# Power.net
KiCad netlist of a schematic drawn in Altium Designer
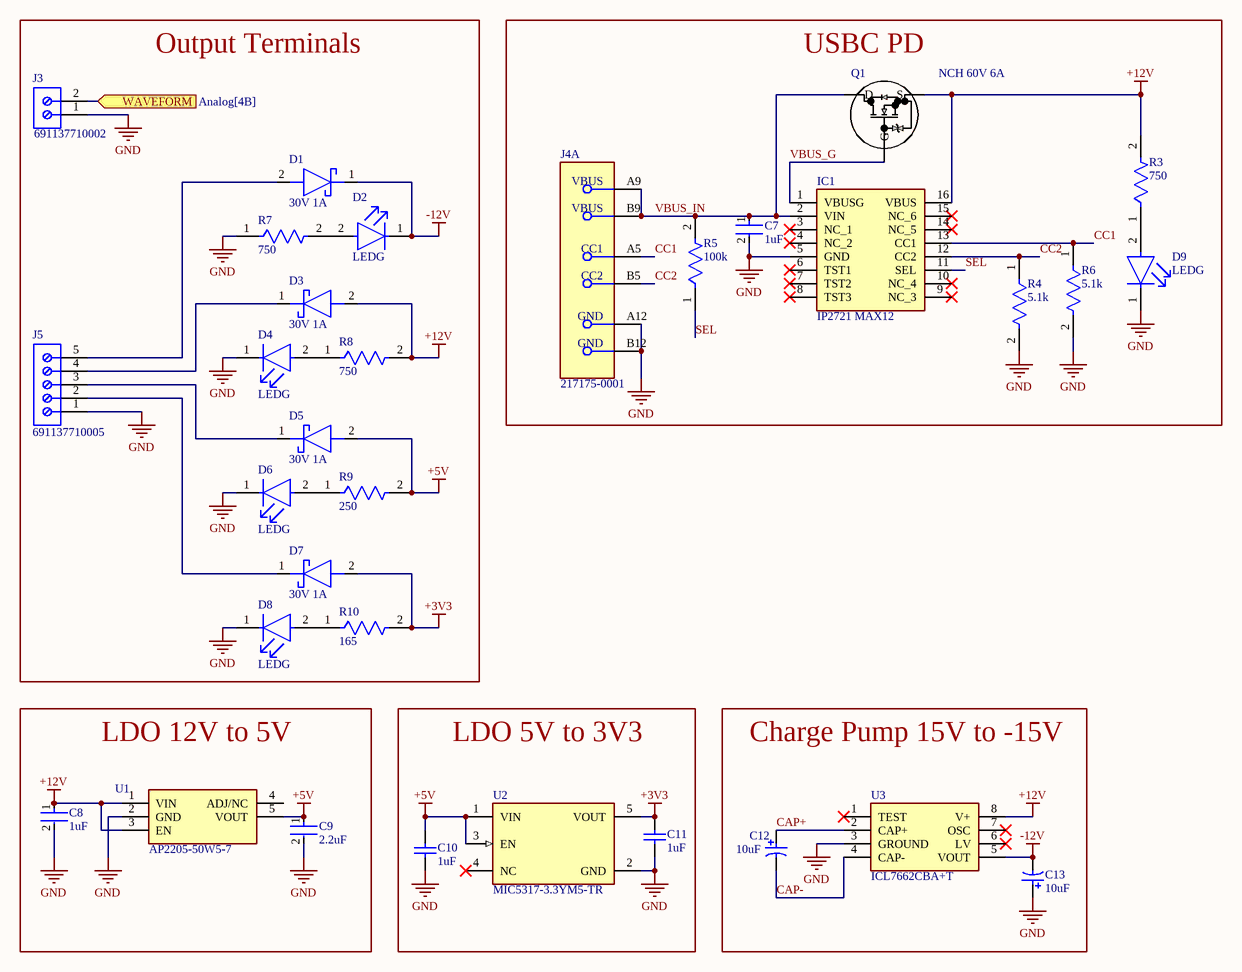
[diagram p0: Power.SchDoc]

(export (version "E")
  (design (tool "Eeschema 10.0.6"))
  (components
    (comp (ref "C7")
      (value "1uF")
      (footprint "FP-CGA5L-0_3-0_1-IPC_B")
      (description "Cap Ceramic 1uF 25V X7R 20% Pad SMD 1206 +125°C Automotive T/R")
      (fields (field (name "TOLERANCE") "20%"))
      (libsource (lib "Altium Content Vault") (part "b4654b650e69147ec39a6b967a45e02"))
    )
    (comp (ref "C8")
      (value "1uF")
      (footprint "FP-CGA5L-0_3-0_1-IPC_B")
      (description "Cap Ceramic 1uF 25V X7R 20% Pad SMD 1206 +125°C Automotive T/R")
      (fields (field (name "TOLERANCE") "20%"))
      (libsource (lib "Altium Content Vault") (part "b4654b650e69147ec39a6b967a45e02"))
    )
    (comp (ref "C9")
      (value "2.2uF")
      (footprint "FP-C0402-BB-MFG")
      (description "C0402")
      (fields
        (field (name "OCTOPART") "https://octopart.com/c0402c132k8gactu-kemet-56745629")
        (field (name "TOLERANCE") "0.1")
      )
      (libsource (lib "Altium Content Vault") (part "b4654b650e69147ec39a6b967a45e02"))
    )
    (comp (ref "C10")
      (value "1uF")
      (footprint "CAPC1206(3216)130_N")
      (description "CAP 1uF 10V ±5% 1206 (3216 Metric) Thickness 1.3mm SMD")
      (fields (field (name "TOLERANCE") "Â±5%"))
      (libsource (lib "Altium Content Vault") (part "CAP"))
    )
    (comp (ref "C11")
      (value "1uF")
      (footprint "CAPC1206(3216)130_N")
      (description "CAP 1uF 10V ±5% 1206 (3216 Metric) Thickness 1.3mm SMD")
      (fields (field (name "TOLERANCE") "Â±5%"))
      (libsource (lib "Altium Content Vault") (part "CAP"))
    )
    (comp (ref "C12")
      (value "10uF")
      (footprint "VISH-293D-E_L")
      (fields (field (name "MANUFACTURER") "Vishay") (field (name "VOLTAGE") "50VDC"))
      (libsource (lib "Altium Content Vault") (part "CAP-P-2"))
    )
    (comp (ref "C13")
      (value "10uF")
      (footprint "VISH-293D-E_L")
      (fields (field (name "MANUFACTURER") "Vishay") (field (name "VOLTAGE") "50VDC"))
      (libsource (lib "Altium Content Vault") (part "CAP-P-2"))
    )
    (comp (ref "D1")
      (value "30V 1A")
      (footprint "SamacSys:1SS357TPH3F")
      (description "Schottky Diode")
      (fields
        (field (name "MANUFACTURER_PART_NUMBER") "CUS10S30,H3F")
        (field (name "MOUSER PART NUMBER") "757-CUS10S30H3F")
      )
      (libsource (lib "*") (part "CUS10S30,H3F"))
    )
    (comp (ref "D2")
      (value "LEDG")
      (footprint "FP-LTST-C170GKT-MFG")
      (description "LED GREEN CLEAR SMD")
      (fields (field (name "VOLTAGE") "5V"))
      (libsource (lib "Altium Content Vault") (part "8706943c75ba83719d021d2fdc84c58"))
    )
    (comp (ref "D3")
      (value "30V 1A")
      (footprint "SamacSys:1SS357TPH3F")
      (description "Schottky Diode")
      (fields
        (field (name "MANUFACTURER_PART_NUMBER") "CUS10S30,H3F")
        (field (name "MOUSER PART NUMBER") "757-CUS10S30H3F")
      )
      (libsource (lib "*") (part "CUS10S30,H3F"))
    )
    (comp (ref "D4")
      (value "LEDG")
      (footprint "FP-LTST-C170GKT-MFG")
      (description "LED GREEN CLEAR SMD")
      (fields (field (name "VOLTAGE") "5V"))
      (libsource (lib "Altium Content Vault") (part "8706943c75ba83719d021d2fdc84c58"))
    )
    (comp (ref "D5")
      (value "30V 1A")
      (footprint "SamacSys:1SS357TPH3F")
      (description "Schottky Diode")
      (fields
        (field (name "MANUFACTURER_PART_NUMBER") "CUS10S30,H3F")
        (field (name "MOUSER PART NUMBER") "757-CUS10S30H3F")
      )
      (libsource (lib "*") (part "CUS10S30,H3F"))
    )
    (comp (ref "D6")
      (value "LEDG")
      (footprint "FP-LTST-C170GKT-MFG")
      (description "LED GREEN CLEAR SMD")
      (fields (field (name "VOLTAGE") "5V"))
      (libsource (lib "Altium Content Vault") (part "8706943c75ba83719d021d2fdc84c58"))
    )
    (comp (ref "D7")
      (value "30V 1A")
      (footprint "SamacSys:1SS357TPH3F")
      (description "Schottky Diode")
      (fields
        (field (name "MANUFACTURER_PART_NUMBER") "CUS10S30,H3F")
        (field (name "MOUSER PART NUMBER") "757-CUS10S30H3F")
      )
      (libsource (lib "*") (part "CUS10S30,H3F"))
    )
    (comp (ref "D8")
      (value "LEDG")
      (footprint "FP-LTST-C170GKT-MFG")
      (description "LED GREEN CLEAR SMD")
      (fields (field (name "VOLTAGE") "5V"))
      (libsource (lib "Altium Content Vault") (part "8706943c75ba83719d021d2fdc84c58"))
    )
    (comp (ref "D9")
      (value "LEDG")
      (footprint "FP-LTST-C170GKT-MFG")
      (description "LED GREEN CLEAR SMD")
      (fields (field (name "VOLTAGE") "5V"))
      (libsource (lib "Altium Content Vault") (part "8706943c75ba83719d021d2fdc84c58"))
    )
    (comp (ref "IC1")
      (value "IP2721 MAX12")
      (footprint "SamacSys:SOP65P640X120-16N")
      (description "Integrated Circuit")
      (fields (field (name "MANUFACTURER_PART_NUMBER") "IP2721"))
      (libsource (lib "*") (part "IP2721"))
    )
    (comp (ref "J3")
      (value "691137710002")
      (footprint "691137710002")
      (libsource (lib "Altium Content Vault") (part "TBL - 1R - 02P - Screw"))
    )
    (comp (ref "J4")
      (value "217175-0001")
      (footprint "FP-217175-0001-MFG")
      (description "CONN RCP USB2.0 C 6+18P SMD RA")
      (libsource (lib "Altium Content Vault") (part "6a66c69350f09309f94811689c98437"))
    )
    (comp (ref "J5")
      (value "691137710005")
      (footprint "691137710005")
      (libsource (lib "Altium Content Vault") (part "TBL - 1R - 05P - Screw"))
    )
    (comp (ref "Q1")
      (value "NCH 60V 6A")
      (footprint "SOT-323F_2-2U1S_UFM_TOS")
      (description "N-ch MOSFET, 60 V, 6.0 A, 0.036 Î©@10V, SOT-323F(UFM)")
      (fields
        (field (name "MANUFACTURER_PART_NUMBER") "SSM3K341TU,LF")
        (field (name "COPYRIGHT") "Copyright (C) 2025 Ultra Librarian. All rights reserved.")
      )
      (libsource (lib "Connectors") (part "SSM3K341TU,LF"))
    )
    (comp (ref "R3")
      (value "750")
      (footprint "FP-AT0805-IPC_C")
      (description "Thin Film Chip Resistors Automotive Grade 10kΩ 0.1% 50ppm/°C 0805")
      (libsource (lib "Altium Content Vault") (part "1029c3af85768c4190bb7ad29bc67b5"))
    )
    (comp (ref "R4")
      (value "5.1k")
      (footprint "FP-TFCR0603-IPC_A")
      (description "RES Thin Film,  5.1kΩ, 0.25%, 0.1W, 25ppm/°C, 0603")
      (libsource (lib "Altium Content Vault") (part "1029c3af85768c4190bb7ad29bc67b5"))
    )
    (comp (ref "R5")
      (value "100k")
      (footprint "FP-MCU0805-IPC_B")
      (description "0805")
      (libsource (lib "Altium Content Vault") (part "1029c3af85768c4190bb7ad29bc67b5"))
    )
    (comp (ref "R6")
      (value "5.1k")
      (footprint "FP-TFCR0603-IPC_A")
      (description "RES Thin Film,  5.1kΩ, 0.25%, 0.1W, 25ppm/°C, 0603")
      (libsource (lib "Altium Content Vault") (part "1029c3af85768c4190bb7ad29bc67b5"))
    )
    (comp (ref "R7")
      (value "750")
      (footprint "FP-RMCF0805-MFG")
      (description "6.8kΩ ±5% 0.125W 0805 Thick Film Chip Resistor AEC-Q200 compliant")
      (fields (field (name "TOLERANCE") "5%"))
      (libsource (lib "Altium Content Vault") (part "1029c3af85768c4190bb7ad29bc67b5"))
    )
    (comp (ref "R8")
      (value "750")
      (footprint "FP-RMCF0805-MFG")
      (description "6.8kΩ ±5% 0.125W 0805 Thick Film Chip Resistor AEC-Q200 compliant")
      (fields (field (name "TOLERANCE") "5%"))
      (libsource (lib "Altium Content Vault") (part "1029c3af85768c4190bb7ad29bc67b5"))
    )
    (comp (ref "R9")
      (value "250")
      (footprint "FP-RMCF0805-MFG")
      (description "0805 250 Ohms 0.25W")
      (fields (field (name "TOLERANCE") "5%"))
      (libsource (lib "Altium Content Vault") (part "1029c3af85768c4190bb7ad29bc67b5"))
    )
    (comp (ref "R10")
      (value "165")
      (footprint "FP-TFCR0603-IPC_B")
      (description "RES Thin Film,  620Ω, 0.25%, 0.1W, 25ppm/°C, 0603")
      (libsource (lib "Altium Content Vault") (part "1029c3af85768c4190bb7ad29bc67b5"))
    )
    (comp (ref "U1")
      (value "AP2205-50W5-7")
      (footprint "SamacSys:SOT95P285X140-5N")
      (description "Integrated Circuit")
      (fields (field (name "MOUSER PART NUMBER") "621-AP2205-50W5-7"))
      (libsource (lib "*") (part "AP2205-50W5-7"))
    )
    (comp (ref "U2")
      (value "MIC5317-3.3YM5-TR")
      (footprint "FP-SOT23-5LD-PL-1-MFG")
      (description "IC REG LINEAR 3.3V 150MA SOT23-5")
      (libsource (lib "Altium Content Vault") (part "0a093dae7315cdc977fd108dde87457"))
    )
    (comp (ref "U3")
      (value "ICL7662CBA+T")
      (footprint "SamacSys:SOIC127P600X175-8N")
      (description "Integrated Circuit")
      (fields (field (name "MOUSER PART NUMBER") "700-ICL7662CBAT"))
      (libsource (lib "*") (part "ICL7662CBA+T"))
    )
  )
  (nets
    (net (code "1") (name "+3V3") (class "Default")
      (node (ref "C11") (pin "2") (pinfunction "2_2") (pintype "passive"))
      (node (ref "D7") (pin "2") (pinfunction "A_2") (pintype "passive"))
      (node (ref "R10") (pin "2") (pinfunction "2_2") (pintype "passive"))
      (node (ref "U2") (pin "5") (pinfunction "VOUT_5") (pintype "power_in"))
    )
    (net (code "2") (name "+5V") (class "Default")
      (node (ref "C10") (pin "2") (pinfunction "2_2") (pintype "passive"))
      (node (ref "C9") (pin "1") (pinfunction "1_1") (pintype "passive"))
      (node (ref "D5") (pin "2") (pinfunction "A_2") (pintype "passive"))
      (node (ref "R9") (pin "2") (pinfunction "2_2") (pintype "passive"))
      (node (ref "U1") (pin "5") (pinfunction "VOUT_5") (pintype "passive"))
      (node (ref "U2") (pin "1") (pinfunction "VIN_1") (pintype "power_in"))
      (node (ref "U2") (pin "3") (pinfunction "EN_3") (pintype "input"))
    )
    (net (code "3") (name "+12V") (class "Default")
      (node (ref "C8") (pin "1") (pinfunction "1_1") (pintype "passive"))
      (node (ref "D3") (pin "2") (pinfunction "A_2") (pintype "passive"))
      (node (ref "IC1") (pin "16") (pinfunction "VBUS_16") (pintype "passive"))
      (node (ref "Q1") (pin "2") (pinfunction "S_2") (pintype "passive"))
      (node (ref "R3") (pin "2") (pinfunction "2_2") (pintype "passive"))
      (node (ref "R8") (pin "2") (pinfunction "2_2") (pintype "passive"))
      (node (ref "U1") (pin "1") (pinfunction "VIN_1") (pintype "passive"))
      (node (ref "U1") (pin "3") (pinfunction "EN_3") (pintype "passive"))
      (node (ref "U3") (pin "8") (pinfunction "V+_8") (pintype "passive"))
    )
    (net (code "4") (name "-12V") (class "Default")
      (node (ref "C13") (pin "2") (pinfunction "2_2") (pintype "passive"))
      (node (ref "D1") (pin "1") (pinfunction "K_1") (pintype "passive"))
      (node (ref "D2") (pin "1") (pinfunction "C_1") (pintype "passive"))
      (node (ref "U3") (pin "5") (pinfunction "VOUT_5") (pintype "passive"))
    )
    (net (code "5") (name "/CAP+") (class "Default")
      (node (ref "C12") (pin "1") (pinfunction "1_1") (pintype "passive"))
      (node (ref "U3") (pin "2") (pinfunction "CAP+_2") (pintype "passive"))
    )
    (net (code "6") (name "/CAP-") (class "Default")
      (node (ref "C12") (pin "2") (pinfunction "2_2") (pintype "passive"))
      (node (ref "U3") (pin "4") (pinfunction "CAP-_4") (pintype "passive"))
    )
    (net (code "7") (name "/CC1") (class "Default")
      (node (ref "IC1") (pin "13") (pinfunction "CC1_13") (pintype "passive"))
      (node (ref "J4") (pin "A5") (pinfunction "CC1_A5") (pintype "passive"))
      (node (ref "R6") (pin "1") (pinfunction "1_1") (pintype "passive"))
    )
    (net (code "8") (name "/CC2") (class "Default")
      (node (ref "IC1") (pin "12") (pinfunction "CC2_12") (pintype "passive"))
      (node (ref "J4") (pin "B5") (pinfunction "CC2_B5") (pintype "passive"))
      (node (ref "R4") (pin "1") (pinfunction "1_1") (pintype "passive"))
    )
    (net (code "9") (name "/SEL") (class "Default")
      (node (ref "IC1") (pin "11") (pinfunction "SEL_11") (pintype "passive"))
      (node (ref "R5") (pin "1") (pinfunction "1_1") (pintype "passive"))
    )
    (net (code "10") (name "/VBUS_G") (class "Default")
      (node (ref "IC1") (pin "1") (pinfunction "VBUSG_1") (pintype "passive"))
      (node (ref "Q1") (pin "1") (pinfunction "G_1") (pintype "passive"))
    )
    (net (code "11") (name "/VBUS_IN") (class "Default")
      (node (ref "C7") (pin "1") (pinfunction "1_1") (pintype "passive"))
      (node (ref "IC1") (pin "2") (pinfunction "VIN_2") (pintype "passive"))
      (node (ref "J4") (pin "A9") (pinfunction "VBUS_A9") (pintype "power_in"))
      (node (ref "J4") (pin "B9") (pinfunction "VBUS_B9") (pintype "power_in"))
      (node (ref "Q1") (pin "3") (pinfunction "D_3") (pintype "passive"))
      (node (ref "R5") (pin "2") (pinfunction "2_2") (pintype "passive"))
    )
    (net (code "12") (name "/WAVEFORM") (class "Default")
      (node (ref "J3") (pin "2") (pinfunction "2_2") (pintype "passive"))
    )
    (net (code "13") (name "GND") (class "Default")
      (node (ref "C10") (pin "1") (pinfunction "1_1") (pintype "passive"))
      (node (ref "C11") (pin "1") (pinfunction "1_1") (pintype "passive"))
      (node (ref "C13") (pin "1") (pinfunction "1_1") (pintype "passive"))
      (node (ref "C7") (pin "2") (pinfunction "2_2") (pintype "passive"))
      (node (ref "C8") (pin "2") (pinfunction "2_2") (pintype "passive"))
      (node (ref "C9") (pin "2") (pinfunction "2_2") (pintype "passive"))
      (node (ref "D4") (pin "1") (pinfunction "C_1") (pintype "passive"))
      (node (ref "D6") (pin "1") (pinfunction "C_1") (pintype "passive"))
      (node (ref "D8") (pin "1") (pinfunction "C_1") (pintype "passive"))
      (node (ref "D9") (pin "1") (pinfunction "C_1") (pintype "passive"))
      (node (ref "IC1") (pin "5") (pinfunction "GND_5") (pintype "passive"))
      (node (ref "J3") (pin "1") (pinfunction "1_1") (pintype "passive"))
      (node (ref "J4") (pin "A12") (pinfunction "GND_A12") (pintype "power_in"))
      (node (ref "J4") (pin "B12") (pinfunction "GND_B12") (pintype "power_in"))
      (node (ref "J5") (pin "1") (pinfunction "1_1") (pintype "passive"))
      (node (ref "R4") (pin "2") (pinfunction "2_2") (pintype "passive"))
      (node (ref "R6") (pin "2") (pinfunction "2_2") (pintype "passive"))
      (node (ref "R7") (pin "1") (pinfunction "1_1") (pintype "passive"))
      (node (ref "U1") (pin "2") (pinfunction "GND_2") (pintype "passive"))
      (node (ref "U2") (pin "2") (pinfunction "GND_2") (pintype "power_in"))
      (node (ref "U3") (pin "3") (pinfunction "GROUND_3") (pintype "passive"))
    )
    (net (code "14") (name "Net-(D1-A)") (class "Default")
      (node (ref "D1") (pin "2") (pinfunction "A_2") (pintype "passive"))
      (node (ref "J5") (pin "5") (pinfunction "5_5") (pintype "passive"))
    )
    (net (code "15") (name "Net-(D2-A)") (class "Default")
      (node (ref "D2") (pin "2") (pinfunction "A_2") (pintype "passive"))
      (node (ref "R7") (pin "2") (pinfunction "2_2") (pintype "passive"))
    )
    (net (code "16") (name "Net-(D3-K)") (class "Default")
      (node (ref "D3") (pin "1") (pinfunction "K_1") (pintype "passive"))
      (node (ref "J5") (pin "4") (pinfunction "4_4") (pintype "passive"))
    )
    (net (code "17") (name "Net-(D4-A)") (class "Default")
      (node (ref "D4") (pin "2") (pinfunction "A_2") (pintype "passive"))
      (node (ref "R8") (pin "1") (pinfunction "1_1") (pintype "passive"))
    )
    (net (code "18") (name "Net-(D5-K)") (class "Default")
      (node (ref "D5") (pin "1") (pinfunction "K_1") (pintype "passive"))
      (node (ref "J5") (pin "3") (pinfunction "3_3") (pintype "passive"))
    )
    (net (code "19") (name "Net-(D6-A)") (class "Default")
      (node (ref "D6") (pin "2") (pinfunction "A_2") (pintype "passive"))
      (node (ref "R9") (pin "1") (pinfunction "1_1") (pintype "passive"))
    )
    (net (code "20") (name "Net-(D7-K)") (class "Default")
      (node (ref "D7") (pin "1") (pinfunction "K_1") (pintype "passive"))
      (node (ref "J5") (pin "2") (pinfunction "2_2") (pintype "passive"))
    )
    (net (code "21") (name "Net-(D8-A)") (class "Default")
      (node (ref "D8") (pin "2") (pinfunction "A_2") (pintype "passive"))
      (node (ref "R10") (pin "1") (pinfunction "1_1") (pintype "passive"))
    )
    (net (code "22") (name "Net-(D9-A)") (class "Default")
      (node (ref "D9") (pin "2") (pinfunction "A_2") (pintype "passive"))
      (node (ref "R3") (pin "1") (pinfunction "1_1") (pintype "passive"))
    )
    (net (code "23") (name "unconnected-(IC1-NC_1-Pad3)") (class "Default")
      (node (ref "IC1") (pin "3") (pinfunction "NC_1_3") (pintype "passive+no_connect"))
    )
    (net (code "24") (name "unconnected-(IC1-NC_2-Pad4)") (class "Default")
      (node (ref "IC1") (pin "4") (pinfunction "NC_2_4") (pintype "passive+no_connect"))
    )
    (net (code "25") (name "unconnected-(IC1-NC_3-Pad9)") (class "Default")
      (node (ref "IC1") (pin "9") (pinfunction "NC_3_9") (pintype "passive+no_connect"))
    )
    (net (code "26") (name "unconnected-(IC1-NC_4-Pad10)") (class "Default")
      (node (ref "IC1") (pin "10") (pinfunction "NC_4_10") (pintype "passive+no_connect"))
    )
    (net (code "27") (name "unconnected-(IC1-NC_5-Pad14)") (class "Default")
      (node (ref "IC1") (pin "14") (pinfunction "NC_5_14") (pintype "passive+no_connect"))
    )
    (net (code "28") (name "unconnected-(IC1-NC_6-Pad15)") (class "Default")
      (node (ref "IC1") (pin "15") (pinfunction "NC_6_15") (pintype "passive+no_connect"))
    )
    (net (code "29") (name "unconnected-(IC1-TST1-Pad6)") (class "Default")
      (node (ref "IC1") (pin "6") (pinfunction "TST1_6") (pintype "passive+no_connect"))
    )
    (net (code "30") (name "unconnected-(IC1-TST2-Pad7)") (class "Default")
      (node (ref "IC1") (pin "7") (pinfunction "TST2_7") (pintype "passive+no_connect"))
    )
    (net (code "31") (name "unconnected-(IC1-TST3-Pad8)") (class "Default")
      (node (ref "IC1") (pin "8") (pinfunction "TST3_8") (pintype "passive+no_connect"))
    )
    (net (code "32") (name "unconnected-(U1-ADJ{slash}NC-Pad4)") (class "Default")
      (node (ref "U1") (pin "4") (pinfunction "ADJ/NC_4") (pintype "passive"))
    )
    (net (code "33") (name "unconnected-(U2-NC-Pad4)") (class "Default")
      (node (ref "U2") (pin "4") (pinfunction "NC_4") (pintype "passive+no_connect"))
    )
    (net (code "34") (name "unconnected-(U3-LV-Pad6)") (class "Default")
      (node (ref "U3") (pin "6") (pinfunction "LV_6") (pintype "passive+no_connect"))
    )
    (net (code "35") (name "unconnected-(U3-OSC-Pad7)") (class "Default")
      (node (ref "U3") (pin "7") (pinfunction "OSC_7") (pintype "passive+no_connect"))
    )
    (net (code "36") (name "unconnected-(U3-TEST-Pad1)") (class "Default")
      (node (ref "U3") (pin "1") (pinfunction "TEST_1") (pintype "passive+no_connect"))
    )
  )
)
